# simple-slave.net
KiCad netlist of a schematic drawn in EAGLE
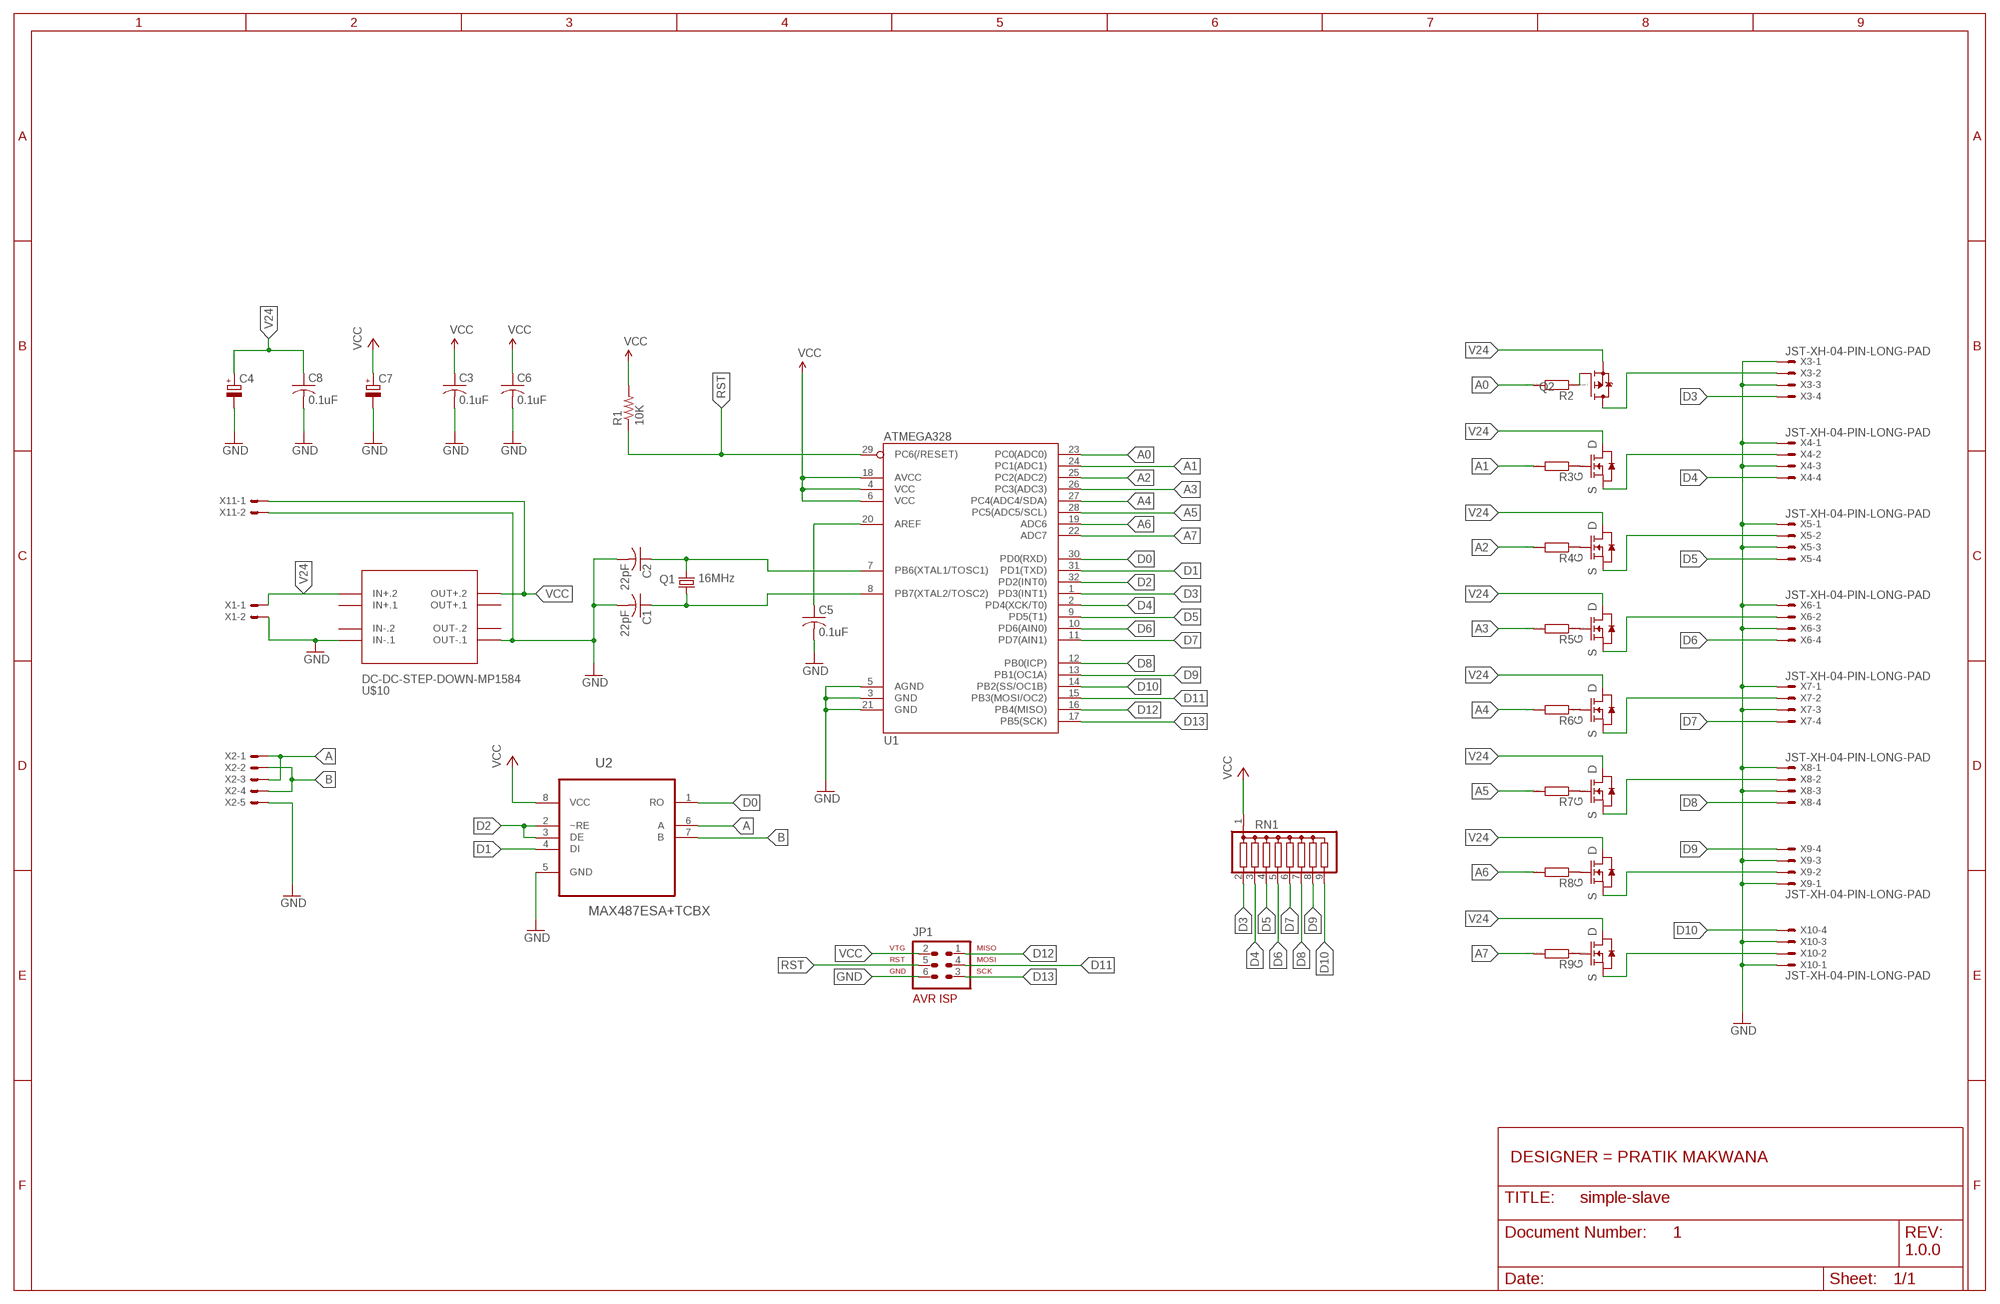
[diagram p0: schematic, sheet 1]

(export (version "E")
  (design (tool "Eeschema 10.0.6"))
  (components
    (comp (ref "C1")
      (value "22pF")
      (footprint "eagle-import:C1206")
      (libsource (lib "eagle-import") (part "C-USC1206"))
    )
    (comp (ref "C2")
      (value "22pF")
      (footprint "eagle-import:C1206")
      (libsource (lib "eagle-import") (part "C-USC1206"))
    )
    (comp (ref "C3")
      (value "0.1uF")
      (footprint "eagle-import:C0805")
      (libsource (lib "eagle-import") (part "C-USC0805"))
    )
    (comp (ref "C4")
      (value "CPOL-EUSANYO_SMD_C6")
      (footprint "eagle-import:SANYO-OSCON_SMD_C6")
      (libsource (lib "eagle-import") (part "CPOL-EUSANYO_SMD_C6"))
    )
    (comp (ref "C5")
      (value "0.1uF")
      (footprint "eagle-import:C0805")
      (libsource (lib "eagle-import") (part "C-USC0805"))
    )
    (comp (ref "C6")
      (value "0.1uF")
      (footprint "eagle-import:C0805")
      (libsource (lib "eagle-import") (part "C-USC0805"))
    )
    (comp (ref "C7")
      (value "CPOL-EUSANYO_SMD_C6")
      (footprint "eagle-import:SANYO-OSCON_SMD_C6")
      (libsource (lib "eagle-import") (part "CPOL-EUSANYO_SMD_C6"))
    )
    (comp (ref "C8")
      (value "0.1uF")
      (footprint "eagle-import:C0805")
      (libsource (lib "eagle-import") (part "C-USC0805"))
    )
    (comp (ref "JP1")
      (value "AVR-ISP-6")
      (footprint "eagle-import:AVR-ISP-6")
      (libsource (lib "eagle-import") (part "AVR-ISP-6"))
    )
    (comp (ref "Q1")
      (value "16MHz")
      (footprint "eagle-import:HC49_S")
      (libsource (lib "eagle-import") (part "CRYTALHC49S"))
    )
    (comp (ref "Q2")
      (value "SPD30P06PTO252")
      (footprint "eagle-import:TO252")
      (libsource (lib "eagle-import") (part "SPD30P06PTO252"))
    )
    (comp (ref "R1")
      (value "10K")
      (footprint "eagle-import:R1206")
      (libsource (lib "eagle-import") (part "R-US_R1206"))
    )
    (comp (ref "R2")
      (value "RR1206")
      (footprint "eagle-import:R1206")
      (libsource (lib "eagle-import") (part "RR1206"))
    )
    (comp (ref "R3")
      (value "RR1206")
      (footprint "eagle-import:R1206")
      (libsource (lib "eagle-import") (part "RR1206"))
    )
    (comp (ref "R4")
      (value "RR1206")
      (footprint "eagle-import:R1206")
      (libsource (lib "eagle-import") (part "RR1206"))
    )
    (comp (ref "R5")
      (value "RR1206")
      (footprint "eagle-import:R1206")
      (libsource (lib "eagle-import") (part "RR1206"))
    )
    (comp (ref "R6")
      (value "RR1206")
      (footprint "eagle-import:R1206")
      (libsource (lib "eagle-import") (part "RR1206"))
    )
    (comp (ref "R7")
      (value "RR1206")
      (footprint "eagle-import:R1206")
      (libsource (lib "eagle-import") (part "RR1206"))
    )
    (comp (ref "R8")
      (value "RR1206")
      (footprint "eagle-import:R1206")
      (libsource (lib "eagle-import") (part "RR1206"))
    )
    (comp (ref "R9")
      (value "RR1206")
      (footprint "eagle-import:R1206")
      (libsource (lib "eagle-import") (part "RR1206"))
    )
    (comp (ref "RN1")
      (value "G08R")
      (footprint "eagle-import:SIL9")
      (libsource (lib "eagle-import") (part "G08R"))
    )
    (comp (ref "U$2")
      (value "MOSFET-NTO252")
      (footprint "eagle-import:TO252")
      (libsource (lib "eagle-import") (part "MOSFET-NTO252"))
    )
    (comp (ref "U$3")
      (value "MOSFET-NTO252")
      (footprint "eagle-import:TO252")
      (libsource (lib "eagle-import") (part "MOSFET-NTO252"))
    )
    (comp (ref "U$4")
      (value "MOSFET-NTO252")
      (footprint "eagle-import:TO252")
      (libsource (lib "eagle-import") (part "MOSFET-NTO252"))
    )
    (comp (ref "U$5")
      (value "MOSFET-NTO252")
      (footprint "eagle-import:TO252")
      (libsource (lib "eagle-import") (part "MOSFET-NTO252"))
    )
    (comp (ref "U$6")
      (value "MOSFET-NTO252")
      (footprint "eagle-import:TO252")
      (libsource (lib "eagle-import") (part "MOSFET-NTO252"))
    )
    (comp (ref "U$7")
      (value "MOSFET-NTO252")
      (footprint "eagle-import:TO252")
      (libsource (lib "eagle-import") (part "MOSFET-NTO252"))
    )
    (comp (ref "U$8")
      (value "MOSFET-NTO252")
      (footprint "eagle-import:TO252")
      (libsource (lib "eagle-import") (part "MOSFET-NTO252"))
    )
    (comp (ref "U$10")
      (value "DC-DC-STEP-DOWN-MP1584")
      (footprint "eagle-import:DC-DC-STEP-DOWN-MP1584")
      (libsource (lib "eagle-import") (part "DC-DC-STEP-DOWN-MP1584"))
    )
    (comp (ref "U1")
      (value "ATMEGA328")
      (footprint "eagle-import:TQFP32-08")
      (libsource (lib "eagle-import") (part "ATMEGA328"))
    )
    (comp (ref "U2")
      (value "MAX487ESA+TCBX")
      (footprint "eagle-import:SOIC127P600X175-8N")
      (fields (field (name "MF") "Maxim Integrated"))
      (libsource (lib "eagle-import") (part "MAX487ESA+TCBX"))
    )
    (comp (ref "X1")
      (value "JST-XH-02-PIN-LONG-PAD")
      (footprint "eagle-import:JST-XH-02-PACKAGE-LONG-PAD")
      (libsource (lib "eagle-import") (part "JST-XH-02-PIN-LONG-PAD"))
    )
    (comp (ref "X2")
      (value "JST-XH-05-PIN-LONG-PAD")
      (footprint "eagle-import:JST-XH-05-PACKAGE-LONG-PAD")
      (libsource (lib "eagle-import") (part "JST-XH-05-PIN-LONG-PAD"))
    )
    (comp (ref "X3")
      (value "JST-XH-04-PIN-LONG-PAD")
      (footprint "eagle-import:JST-XH-04-PACKAGE-LONG-PAD")
      (libsource (lib "eagle-import") (part "JST-XH-04-PIN-LONG-PAD"))
    )
    (comp (ref "X4")
      (value "JST-XH-04-PIN-LONG-PAD")
      (footprint "eagle-import:JST-XH-04-PACKAGE-LONG-PAD")
      (libsource (lib "eagle-import") (part "JST-XH-04-PIN-LONG-PAD"))
    )
    (comp (ref "X5")
      (value "JST-XH-04-PIN-LONG-PAD")
      (footprint "eagle-import:JST-XH-04-PACKAGE-LONG-PAD")
      (libsource (lib "eagle-import") (part "JST-XH-04-PIN-LONG-PAD"))
    )
    (comp (ref "X6")
      (value "JST-XH-04-PIN-LONG-PAD")
      (footprint "eagle-import:JST-XH-04-PACKAGE-LONG-PAD")
      (libsource (lib "eagle-import") (part "JST-XH-04-PIN-LONG-PAD"))
    )
    (comp (ref "X7")
      (value "JST-XH-04-PIN-LONG-PAD")
      (footprint "eagle-import:JST-XH-04-PACKAGE-LONG-PAD")
      (libsource (lib "eagle-import") (part "JST-XH-04-PIN-LONG-PAD"))
    )
    (comp (ref "X8")
      (value "JST-XH-04-PIN-LONG-PAD")
      (footprint "eagle-import:JST-XH-04-PACKAGE-LONG-PAD")
      (libsource (lib "eagle-import") (part "JST-XH-04-PIN-LONG-PAD"))
    )
    (comp (ref "X9")
      (value "JST-XH-04-PIN-LONG-PAD")
      (footprint "eagle-import:JST-XH-04-PACKAGE-LONG-PAD")
      (libsource (lib "eagle-import") (part "JST-XH-04-PIN-LONG-PAD"))
    )
    (comp (ref "X10")
      (value "JST-XH-04-PIN-LONG-PAD")
      (footprint "eagle-import:JST-XH-04-PACKAGE-LONG-PAD")
      (libsource (lib "eagle-import") (part "JST-XH-04-PIN-LONG-PAD"))
    )
    (comp (ref "X11")
      (value "JST-XH-02-PIN-LONG-PAD")
      (footprint "eagle-import:JST-XH-02-PACKAGE-LONG-PAD")
      (libsource (lib "eagle-import") (part "JST-XH-02-PIN-LONG-PAD"))
    )
  )
  (nets
    (net (code "1") (name "A") (class "Default")
      (node (ref "U2") (pin "6") (pinfunction "A_6") (pintype "bidirectional"))
      (node (ref "X2") (pin "1") (pinfunction "S_1") (pintype "passive"))
      (node (ref "X2") (pin "3") (pinfunction "S_3") (pintype "passive"))
    )
    (net (code "2") (name "A0") (class "Default")
      (node (ref "R2") (pin "2") (pinfunction "2_2") (pintype "passive"))
      (node (ref "U1") (pin "23") (pinfunction "PC0(ADC0)_23") (pintype "bidirectional"))
    )
    (net (code "3") (name "A1") (class "Default")
      (node (ref "R3") (pin "2") (pinfunction "2_2") (pintype "passive"))
      (node (ref "U1") (pin "24") (pinfunction "PC1(ADC1)_24") (pintype "bidirectional"))
    )
    (net (code "4") (name "A2") (class "Default")
      (node (ref "R4") (pin "2") (pinfunction "2_2") (pintype "passive"))
      (node (ref "U1") (pin "25") (pinfunction "PC2(ADC2)_25") (pintype "bidirectional"))
    )
    (net (code "5") (name "A3") (class "Default")
      (node (ref "R5") (pin "2") (pinfunction "2_2") (pintype "passive"))
      (node (ref "U1") (pin "26") (pinfunction "PC3(ADC3)_26") (pintype "bidirectional"))
    )
    (net (code "6") (name "A4") (class "Default")
      (node (ref "R6") (pin "2") (pinfunction "2_2") (pintype "passive"))
      (node (ref "U1") (pin "27") (pinfunction "PC4(ADC4/SDA)_27") (pintype "bidirectional"))
    )
    (net (code "7") (name "A5") (class "Default")
      (node (ref "R7") (pin "2") (pinfunction "2_2") (pintype "passive"))
      (node (ref "U1") (pin "28") (pinfunction "PC5(ADC5/SCL)_28") (pintype "bidirectional"))
    )
    (net (code "8") (name "A6") (class "Default")
      (node (ref "R8") (pin "2") (pinfunction "2_2") (pintype "passive"))
      (node (ref "U1") (pin "19") (pinfunction "ADC6_19") (pintype "bidirectional"))
    )
    (net (code "9") (name "A7") (class "Default")
      (node (ref "R9") (pin "2") (pinfunction "2_2") (pintype "passive"))
      (node (ref "U1") (pin "22") (pinfunction "ADC7_22") (pintype "bidirectional"))
    )
    (net (code "10") (name "B") (class "Default")
      (node (ref "U2") (pin "7") (pinfunction "B_7") (pintype "bidirectional"))
      (node (ref "X2") (pin "2") (pinfunction "S_2") (pintype "passive"))
      (node (ref "X2") (pin "4") (pinfunction "S_4") (pintype "passive"))
    )
    (net (code "11") (name "D0") (class "Default")
      (node (ref "U1") (pin "30") (pinfunction "PD0(RXD)_30") (pintype "bidirectional"))
      (node (ref "U2") (pin "1") (pinfunction "RO_1") (pintype "output"))
    )
    (net (code "12") (name "D1") (class "Default")
      (node (ref "U1") (pin "31") (pinfunction "PD1(TXD)_31") (pintype "bidirectional"))
      (node (ref "U2") (pin "4") (pinfunction "DI_4") (pintype "input"))
    )
    (net (code "13") (name "D2") (class "Default")
      (node (ref "U1") (pin "32") (pinfunction "PD2(INT0)_32") (pintype "bidirectional"))
      (node (ref "U2") (pin "2") (pinfunction "~{RE}_2") (pintype "input"))
      (node (ref "U2") (pin "3") (pinfunction "DE_3") (pintype "input"))
    )
    (net (code "14") (name "D3") (class "Default")
      (node (ref "RN1") (pin "2") (pinfunction "2_2") (pintype "passive"))
      (node (ref "U1") (pin "1") (pinfunction "PD3(INT1)_1") (pintype "bidirectional"))
      (node (ref "X3") (pin "4") (pinfunction "S_4") (pintype "passive"))
    )
    (net (code "15") (name "D4") (class "Default")
      (node (ref "RN1") (pin "3") (pinfunction "3_3") (pintype "passive"))
      (node (ref "U1") (pin "2") (pinfunction "PD4(XCK/T0)_2") (pintype "bidirectional"))
      (node (ref "X4") (pin "4") (pinfunction "S_4") (pintype "passive"))
    )
    (net (code "16") (name "D5") (class "Default")
      (node (ref "RN1") (pin "4") (pinfunction "4_4") (pintype "passive"))
      (node (ref "U1") (pin "9") (pinfunction "PD5(T1)_9") (pintype "bidirectional"))
      (node (ref "X5") (pin "4") (pinfunction "S_4") (pintype "passive"))
    )
    (net (code "17") (name "D6") (class "Default")
      (node (ref "RN1") (pin "5") (pinfunction "5_5") (pintype "passive"))
      (node (ref "U1") (pin "10") (pinfunction "PD6(AIN0)_10") (pintype "bidirectional"))
      (node (ref "X6") (pin "4") (pinfunction "S_4") (pintype "passive"))
    )
    (net (code "18") (name "D7") (class "Default")
      (node (ref "RN1") (pin "6") (pinfunction "6_6") (pintype "passive"))
      (node (ref "U1") (pin "11") (pinfunction "PD7(AIN1)_11") (pintype "bidirectional"))
      (node (ref "X7") (pin "4") (pinfunction "S_4") (pintype "passive"))
    )
    (net (code "19") (name "D8") (class "Default")
      (node (ref "RN1") (pin "7") (pinfunction "7_7") (pintype "passive"))
      (node (ref "U1") (pin "12") (pinfunction "PB0(ICP)_12") (pintype "bidirectional"))
      (node (ref "X8") (pin "4") (pinfunction "S_4") (pintype "passive"))
    )
    (net (code "20") (name "D9") (class "Default")
      (node (ref "RN1") (pin "8") (pinfunction "8_8") (pintype "passive"))
      (node (ref "U1") (pin "13") (pinfunction "PB1(OC1A)_13") (pintype "bidirectional"))
      (node (ref "X9") (pin "4") (pinfunction "S_4") (pintype "passive"))
    )
    (net (code "21") (name "D10") (class "Default")
      (node (ref "RN1") (pin "9") (pinfunction "9_9") (pintype "passive"))
      (node (ref "U1") (pin "14") (pinfunction "PB2(SS/OC1B)_14") (pintype "bidirectional"))
      (node (ref "X10") (pin "4") (pinfunction "S_4") (pintype "passive"))
    )
    (net (code "22") (name "D11") (class "Default")
      (node (ref "JP1") (pin "4") (pinfunction "4_4") (pintype "passive"))
      (node (ref "U1") (pin "15") (pinfunction "PB3(MOSI/OC2)_15") (pintype "bidirectional"))
    )
    (net (code "23") (name "D12") (class "Default")
      (node (ref "JP1") (pin "1") (pinfunction "1_1") (pintype "passive"))
      (node (ref "U1") (pin "16") (pinfunction "PB4(MISO)_16") (pintype "bidirectional"))
    )
    (net (code "24") (name "D13") (class "Default")
      (node (ref "JP1") (pin "3") (pinfunction "3_3") (pintype "passive"))
      (node (ref "U1") (pin "17") (pinfunction "PB5(SCK)_17") (pintype "bidirectional"))
    )
    (net (code "25") (name "GND") (class "Default")
      (node (ref "C1") (pin "2") (pinfunction "2_2") (pintype "passive"))
      (node (ref "C2") (pin "2") (pinfunction "2_2") (pintype "passive"))
      (node (ref "C3") (pin "2") (pinfunction "2_2") (pintype "passive"))
      (node (ref "C4") (pin "-") (pinfunction "-_-") (pintype "passive"))
      (node (ref "C5") (pin "2") (pinfunction "2_2") (pintype "passive"))
      (node (ref "C6") (pin "2") (pinfunction "2_2") (pintype "passive"))
      (node (ref "C7") (pin "-") (pinfunction "-_-") (pintype "passive"))
      (node (ref "C8") (pin "2") (pinfunction "2_2") (pintype "passive"))
      (node (ref "JP1") (pin "6") (pinfunction "6_6") (pintype "passive"))
      (node (ref "U$10") (pin "IN-.1") (pinfunction "IN-.1_IN-.1") (pintype "bidirectional"))
      (node (ref "U$10") (pin "OUT-.1") (pinfunction "OUT-.1_OUT-.1") (pintype "bidirectional"))
      (node (ref "U1") (pin "21") (pinfunction "GND_21") (pintype "bidirectional"))
      (node (ref "U1") (pin "3") (pinfunction "GND_3") (pintype "bidirectional"))
      (node (ref "U1") (pin "5") (pinfunction "AGND_5") (pintype "bidirectional"))
      (node (ref "U2") (pin "5") (pinfunction "GND_5") (pintype "passive"))
      (node (ref "X1") (pin "2") (pinfunction "S_2") (pintype "passive"))
      (node (ref "X10") (pin "1") (pinfunction "S_1") (pintype "passive"))
      (node (ref "X10") (pin "3") (pinfunction "S_3") (pintype "passive"))
      (node (ref "X11") (pin "2") (pinfunction "S_2") (pintype "passive"))
      (node (ref "X2") (pin "5") (pinfunction "S_5") (pintype "passive"))
      (node (ref "X3") (pin "1") (pinfunction "S_1") (pintype "passive"))
      (node (ref "X3") (pin "3") (pinfunction "S_3") (pintype "passive"))
      (node (ref "X4") (pin "1") (pinfunction "S_1") (pintype "passive"))
      (node (ref "X4") (pin "3") (pinfunction "S_3") (pintype "passive"))
      (node (ref "X5") (pin "1") (pinfunction "S_1") (pintype "passive"))
      (node (ref "X5") (pin "3") (pinfunction "S_3") (pintype "passive"))
      (node (ref "X6") (pin "1") (pinfunction "S_1") (pintype "passive"))
      (node (ref "X6") (pin "3") (pinfunction "S_3") (pintype "passive"))
      (node (ref "X7") (pin "1") (pinfunction "S_1") (pintype "passive"))
      (node (ref "X7") (pin "3") (pinfunction "S_3") (pintype "passive"))
      (node (ref "X8") (pin "1") (pinfunction "S_1") (pintype "passive"))
      (node (ref "X8") (pin "3") (pinfunction "S_3") (pintype "passive"))
      (node (ref "X9") (pin "1") (pinfunction "S_1") (pintype "passive"))
      (node (ref "X9") (pin "3") (pinfunction "S_3") (pintype "passive"))
    )
    (net (code "26") (name "Net-(Q2-D)") (class "Default")
      (node (ref "Q2") (pin "3") (pinfunction "D_3") (pintype "passive"))
      (node (ref "X3") (pin "2") (pinfunction "S_2") (pintype "passive"))
    )
    (net (code "27") (name "Net-(Q2-G)") (class "Default")
      (node (ref "Q2") (pin "1") (pinfunction "G_1") (pintype "passive"))
      (node (ref "R2") (pin "1") (pinfunction "1_1") (pintype "passive"))
    )
    (net (code "28") (name "Net-(U$2-G)") (class "Default")
      (node (ref "R3") (pin "1") (pinfunction "1_1") (pintype "passive"))
      (node (ref "U$2") (pin "P1") (pinfunction "G_P1") (pintype "input"))
    )
    (net (code "29") (name "Net-(U$2-S)") (class "Default")
      (node (ref "U$2") (pin "P3") (pinfunction "S_P3") (pintype "bidirectional"))
      (node (ref "X4") (pin "2") (pinfunction "S_2") (pintype "passive"))
    )
    (net (code "30") (name "Net-(U$3-G)") (class "Default")
      (node (ref "R4") (pin "1") (pinfunction "1_1") (pintype "passive"))
      (node (ref "U$3") (pin "P1") (pinfunction "G_P1") (pintype "input"))
    )
    (net (code "31") (name "Net-(U$3-S)") (class "Default")
      (node (ref "U$3") (pin "P3") (pinfunction "S_P3") (pintype "bidirectional"))
      (node (ref "X5") (pin "2") (pinfunction "S_2") (pintype "passive"))
    )
    (net (code "32") (name "Net-(U$4-G)") (class "Default")
      (node (ref "R5") (pin "1") (pinfunction "1_1") (pintype "passive"))
      (node (ref "U$4") (pin "P1") (pinfunction "G_P1") (pintype "input"))
    )
    (net (code "33") (name "Net-(U$4-S)") (class "Default")
      (node (ref "U$4") (pin "P3") (pinfunction "S_P3") (pintype "bidirectional"))
      (node (ref "X6") (pin "2") (pinfunction "S_2") (pintype "passive"))
    )
    (net (code "34") (name "Net-(U$5-G)") (class "Default")
      (node (ref "R6") (pin "1") (pinfunction "1_1") (pintype "passive"))
      (node (ref "U$5") (pin "P1") (pinfunction "G_P1") (pintype "input"))
    )
    (net (code "35") (name "Net-(U$5-S)") (class "Default")
      (node (ref "U$5") (pin "P3") (pinfunction "S_P3") (pintype "bidirectional"))
      (node (ref "X7") (pin "2") (pinfunction "S_2") (pintype "passive"))
    )
    (net (code "36") (name "Net-(U$6-G)") (class "Default")
      (node (ref "R7") (pin "1") (pinfunction "1_1") (pintype "passive"))
      (node (ref "U$6") (pin "P1") (pinfunction "G_P1") (pintype "input"))
    )
    (net (code "37") (name "Net-(U$6-S)") (class "Default")
      (node (ref "U$6") (pin "P3") (pinfunction "S_P3") (pintype "bidirectional"))
      (node (ref "X8") (pin "2") (pinfunction "S_2") (pintype "passive"))
    )
    (net (code "38") (name "Net-(U$7-G)") (class "Default")
      (node (ref "R8") (pin "1") (pinfunction "1_1") (pintype "passive"))
      (node (ref "U$7") (pin "P1") (pinfunction "G_P1") (pintype "input"))
    )
    (net (code "39") (name "Net-(U$7-S)") (class "Default")
      (node (ref "U$7") (pin "P3") (pinfunction "S_P3") (pintype "bidirectional"))
      (node (ref "X9") (pin "2") (pinfunction "S_2") (pintype "passive"))
    )
    (net (code "40") (name "Net-(U$8-G)") (class "Default")
      (node (ref "R9") (pin "1") (pinfunction "1_1") (pintype "passive"))
      (node (ref "U$8") (pin "P1") (pinfunction "G_P1") (pintype "input"))
    )
    (net (code "41") (name "Net-(U$8-S)") (class "Default")
      (node (ref "U$8") (pin "P3") (pinfunction "S_P3") (pintype "bidirectional"))
      (node (ref "X10") (pin "2") (pinfunction "S_2") (pintype "passive"))
    )
    (net (code "42") (name "Net-(U1-AREF)") (class "Default")
      (node (ref "C5") (pin "1") (pinfunction "1_1") (pintype "passive"))
      (node (ref "U1") (pin "20") (pinfunction "AREF_20") (pintype "bidirectional"))
    )
    (net (code "43") (name "Net-(U1-PB6(XTAL1{slash}TOSC1))") (class "Default")
      (node (ref "C2") (pin "1") (pinfunction "1_1") (pintype "passive"))
      (node (ref "Q1") (pin "2") (pinfunction "2_2") (pintype "passive"))
      (node (ref "U1") (pin "7") (pinfunction "PB6(XTAL1/TOSC1)_7") (pintype "bidirectional"))
    )
    (net (code "44") (name "Net-(U1-PB7(XTAL2{slash}TOSC2))") (class "Default")
      (node (ref "C1") (pin "1") (pinfunction "1_1") (pintype "passive"))
      (node (ref "Q1") (pin "1") (pinfunction "1_1") (pintype "passive"))
      (node (ref "U1") (pin "8") (pinfunction "PB7(XTAL2/TOSC2)_8") (pintype "bidirectional"))
    )
    (net (code "45") (name "RST") (class "Default")
      (node (ref "JP1") (pin "5") (pinfunction "5_5") (pintype "passive"))
      (node (ref "R1") (pin "1") (pinfunction "1_1") (pintype "passive"))
      (node (ref "U1") (pin "29") (pinfunction "PC6(/RESET)_29") (pintype "bidirectional"))
    )
    (net (code "46") (name "V24") (class "Default")
      (node (ref "C4") (pin "+") (pinfunction "+_+") (pintype "passive"))
      (node (ref "C8") (pin "1") (pinfunction "1_1") (pintype "passive"))
      (node (ref "Q2") (pin "2") (pinfunction "S_2") (pintype "passive"))
      (node (ref "U$10") (pin "IN+.2") (pinfunction "IN+.2_IN+.2") (pintype "bidirectional"))
      (node (ref "U$2") (pin "P2") (pinfunction "D_P2") (pintype "bidirectional"))
      (node (ref "U$3") (pin "P2") (pinfunction "D_P2") (pintype "bidirectional"))
      (node (ref "U$4") (pin "P2") (pinfunction "D_P2") (pintype "bidirectional"))
      (node (ref "U$5") (pin "P2") (pinfunction "D_P2") (pintype "bidirectional"))
      (node (ref "U$6") (pin "P2") (pinfunction "D_P2") (pintype "bidirectional"))
      (node (ref "U$7") (pin "P2") (pinfunction "D_P2") (pintype "bidirectional"))
      (node (ref "U$8") (pin "P2") (pinfunction "D_P2") (pintype "bidirectional"))
      (node (ref "X1") (pin "1") (pinfunction "S_1") (pintype "passive"))
    )
    (net (code "47") (name "VCC") (class "Default")
      (node (ref "C3") (pin "1") (pinfunction "1_1") (pintype "passive"))
      (node (ref "C6") (pin "1") (pinfunction "1_1") (pintype "passive"))
      (node (ref "C7") (pin "+") (pinfunction "+_+") (pintype "passive"))
      (node (ref "JP1") (pin "2") (pinfunction "2_2") (pintype "passive"))
      (node (ref "R1") (pin "2") (pinfunction "2_2") (pintype "passive"))
      (node (ref "RN1") (pin "1") (pinfunction "1_1") (pintype "passive"))
      (node (ref "U$10") (pin "OUT+.2") (pinfunction "OUT+.2_OUT+.2") (pintype "bidirectional"))
      (node (ref "U1") (pin "18") (pinfunction "AVCC_18") (pintype "bidirectional"))
      (node (ref "U1") (pin "4") (pinfunction "VCC_4") (pintype "bidirectional"))
      (node (ref "U1") (pin "6") (pinfunction "VCC_6") (pintype "bidirectional"))
      (node (ref "U2") (pin "8") (pinfunction "VCC_8") (pintype "power_in"))
      (node (ref "X11") (pin "1") (pinfunction "S_1") (pintype "passive"))
    )
    (net (code "48") (name "unconnected-(U$10-PadIN+.1)") (class "Default")
      (node (ref "U$10") (pin "IN+.1") (pinfunction "IN+.1_IN+.1") (pintype "bidirectional"))
    )
    (net (code "49") (name "unconnected-(U$10-PadIN-.2)") (class "Default")
      (node (ref "U$10") (pin "IN-.2") (pinfunction "IN-.2_IN-.2") (pintype "bidirectional"))
    )
    (net (code "50") (name "unconnected-(U$10-PadOUT+.1)") (class "Default")
      (node (ref "U$10") (pin "OUT+.1") (pinfunction "OUT+.1_OUT+.1") (pintype "bidirectional"))
    )
    (net (code "51") (name "unconnected-(U$10-PadOUT-.2)") (class "Default")
      (node (ref "U$10") (pin "OUT-.2") (pinfunction "OUT-.2_OUT-.2") (pintype "bidirectional"))
    )
  )
)
